# Microcontroller.net
KiCad netlist of a schematic drawn in Altium Designer
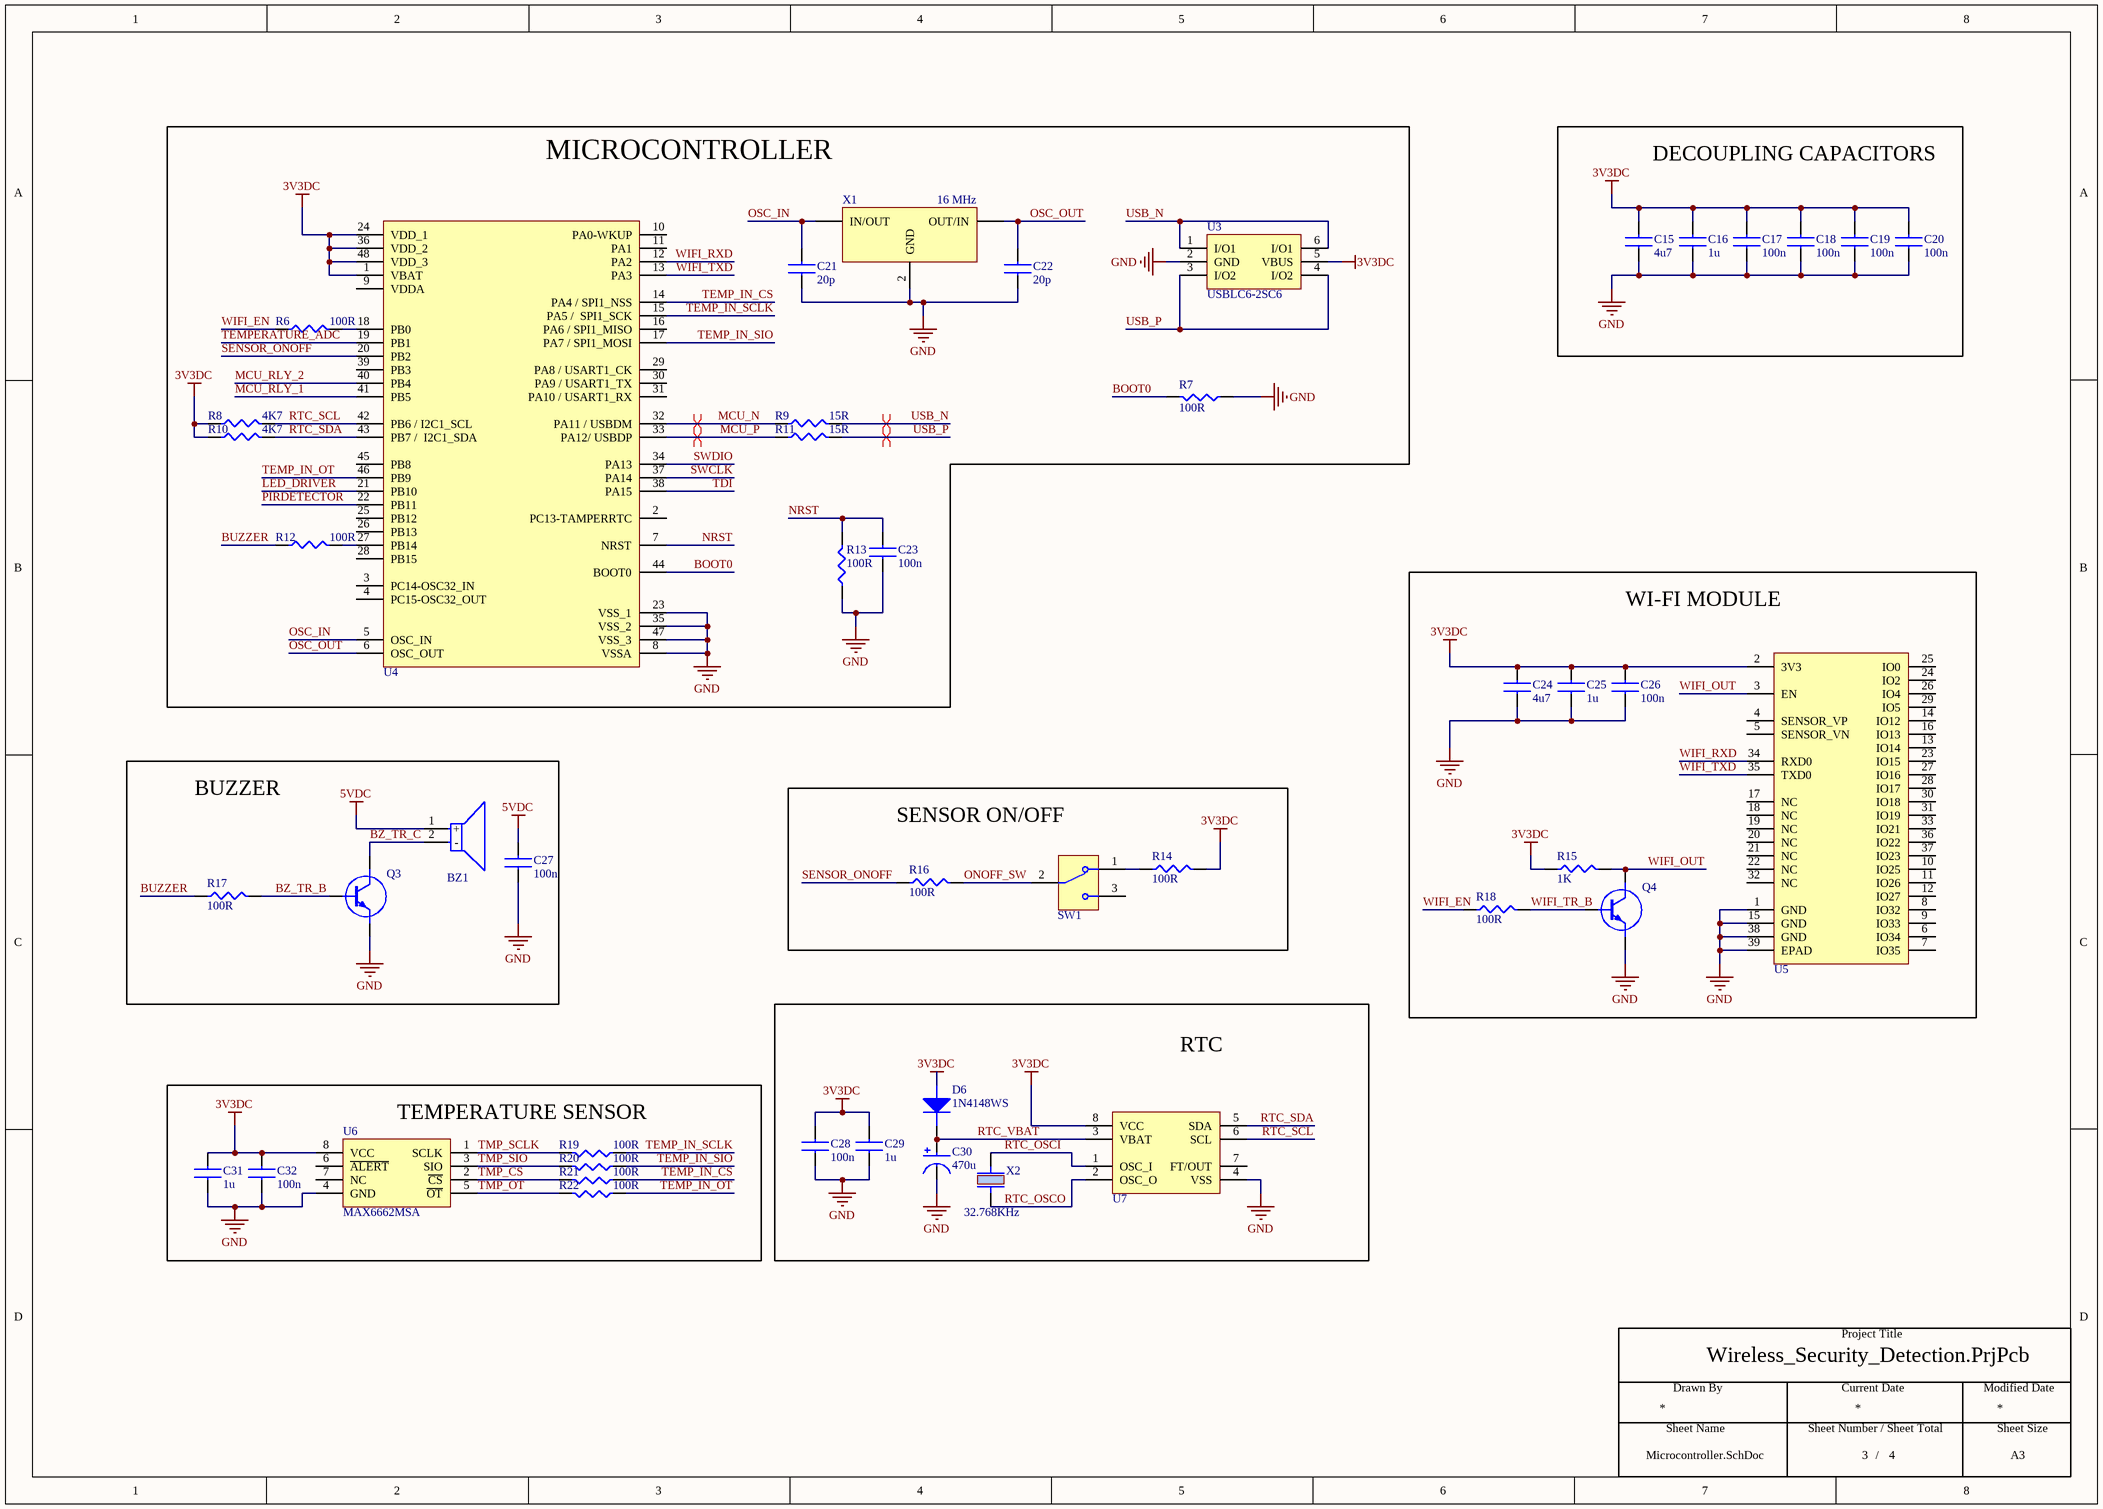
[diagram p0: Microcontroller.SchDoc]

(export (version "E")
  (design (tool "Eeschema 10.0.6"))
  (components
    (comp (ref "BZ1")
      (value "CMI-9605IC-0580T")
      (footprint "CMI-9605IC-0580T")
      (description "Audio Buzzer Magnetic 3VDC 7VDC 30mA 5VDC 85dB 2600Hz to 2800Hz Through Hole Pin Box")
      (fields (field (name "MANUFACTURER") "CUI Devices") (field (name "DESIGNED BY") "UK"))
      (libsource (lib "UKLIB") (part "CMI-9605IC-0580T"))
    )
    (comp (ref "C15")
      (value "4u7")
      (footprint "CAPACITOR 0805 - duplicate")
      (description "Multilayer Ceramic Capacitor, 4.7 uF, 25 V, ± 10%, X5R, 0805 [2012 Metric]")
      (fields
        (field (name "MANUFACTURER") "Samsung")
        (field (name "MANUFACTURER PART NUMBER") "CL21A475KAQNNNE")
        (field (name "DESIGNED BY") "UK")
      )
      (libsource (lib "UKLIB") (part "CAP CER 4.7uF 0805"))
    )
    (comp (ref "C16")
      (value "1u")
      (footprint "CAPACITOR 0805 - duplicate")
      (description "Multilayer Ceramic Capacitor, 1 uF, 50 V, ± 10%, X7R, 0805 [2012 Metric]")
      (fields
        (field (name "MANUFACTURER") "Samsung")
        (field (name "MANUFACTURER PART NUMBER") "CL21B105KBFNNNE")
        (field (name "DESIGNED BY") "UK")
      )
      (libsource (lib "UKLIB") (part "CAP CER 1uF 0805"))
    )
    (comp (ref "C17")
      (value "100n")
      (footprint "Capacitor 0603")
      (description "Multilayer Ceramic Capacitor, 0.1 uF, 50 V, ± 10%, X7R, 0603 [1608 Metric]")
      (fields
        (field (name "MANUFACTURER") "KEMET")
        (field (name "MANUFACTURER PART NUMBER") "C0603C104K5RACTU")
        (field (name "DESIGNED BY") "UK")
      )
      (libsource (lib "UKLIB") (part "CAP CER 100nF 0603"))
    )
    (comp (ref "C18")
      (value "100n")
      (footprint "Capacitor 0603")
      (description "Multilayer Ceramic Capacitor, 0.1 uF, 50 V, ± 10%, X7R, 0603 [1608 Metric]")
      (fields
        (field (name "MANUFACTURER") "KEMET")
        (field (name "MANUFACTURER PART NUMBER") "C0603C104K5RACTU")
        (field (name "DESIGNED BY") "UK")
      )
      (libsource (lib "UKLIB") (part "CAP CER 100nF 0603"))
    )
    (comp (ref "C19")
      (value "100n")
      (footprint "Capacitor 0603")
      (description "Multilayer Ceramic Capacitor, 0.1 uF, 50 V, ± 10%, X7R, 0603 [1608 Metric]")
      (fields
        (field (name "MANUFACTURER") "KEMET")
        (field (name "MANUFACTURER PART NUMBER") "C0603C104K5RACTU")
        (field (name "DESIGNED BY") "UK")
      )
      (libsource (lib "UKLIB") (part "CAP CER 100nF 0603"))
    )
    (comp (ref "C20")
      (value "100n")
      (footprint "Capacitor 0603")
      (description "Multilayer Ceramic Capacitor, 0.1 uF, 50 V, ± 10%, X7R, 0603 [1608 Metric]")
      (fields
        (field (name "MANUFACTURER") "KEMET")
        (field (name "MANUFACTURER PART NUMBER") "C0603C104K5RACTU")
        (field (name "DESIGNED BY") "UK")
      )
      (libsource (lib "UKLIB") (part "CAP CER 100nF 0603"))
    )
    (comp (ref "C21")
      (value "20p")
      (footprint "CAPACITOR 0603")
      (description "Multilayer Ceramic Capacitor, 20 pF, 50 V, ± 5%, C0G (NP0), 0603 [1608 Metric]")
      (fields
        (field (name "MANUFACTURER") "Samsung")
        (field (name "MANUFACTURER PART NUMBER") "CL10C200JB8NNNC")
        (field (name "DESIGNED BY") "UK")
      )
      (libsource (lib "UKLIB") (part "CAP CER 20pF 0603"))
    )
    (comp (ref "C22")
      (value "20p")
      (footprint "CAPACITOR 0603")
      (description "Multilayer Ceramic Capacitor, 20 pF, 50 V, ± 5%, C0G (NP0), 0603 [1608 Metric]")
      (fields
        (field (name "MANUFACTURER") "Samsung")
        (field (name "MANUFACTURER PART NUMBER") "CL10C200JB8NNNC")
        (field (name "DESIGNED BY") "UK")
      )
      (libsource (lib "UKLIB") (part "CAP CER 20pF 0603"))
    )
    (comp (ref "C23")
      (value "100n")
      (footprint "CAPACITOR 0805 - duplicate")
      (description "Multilayer Ceramic Capacitor, 0.1 uF, 50 V, ± 10%, X7R, 0805 [2012 Metric]")
      (fields
        (field (name "MANUFACTURER") "Samsung")
        (field (name "MANUFACTURER PART NUMBER") "CL21B104KBCNNNC")
        (field (name "DESIGNED BY") "UK")
      )
      (libsource (lib "UKLIB") (part "CAP CER 100nF 0805"))
    )
    (comp (ref "C24")
      (value "4u7")
      (footprint "CAPACITOR 0805 - duplicate")
      (description "Multilayer Ceramic Capacitor, 4.7 uF, 25 V, ± 10%, X5R, 0805 [2012 Metric]")
      (fields
        (field (name "MANUFACTURER") "Samsung")
        (field (name "MANUFACTURER PART NUMBER") "CL21A475KAQNNNE")
        (field (name "DESIGNED BY") "UK")
      )
      (libsource (lib "UKLIB") (part "CAP CER 4.7uF 0805"))
    )
    (comp (ref "C25")
      (value "1u")
      (footprint "CAPACITOR 0805 - duplicate")
      (description "Multilayer Ceramic Capacitor, 1 uF, 50 V, ± 10%, X7R, 0805 [2012 Metric]")
      (fields
        (field (name "MANUFACTURER") "Samsung")
        (field (name "MANUFACTURER PART NUMBER") "CL21B105KBFNNNE")
        (field (name "DESIGNED BY") "UK")
      )
      (libsource (lib "UKLIB") (part "CAP CER 1uF 0805"))
    )
    (comp (ref "C26")
      (value "100n")
      (footprint "CAPACITOR 0805 - duplicate")
      (description "Multilayer Ceramic Capacitor, 0.1 uF, 50 V, ± 10%, X7R, 0805 [2012 Metric]")
      (fields
        (field (name "MANUFACTURER") "Samsung")
        (field (name "MANUFACTURER PART NUMBER") "CL21B104KBCNNNC")
        (field (name "DESIGNED BY") "UK")
      )
      (libsource (lib "UKLIB") (part "CAP CER 100nF 0805"))
    )
    (comp (ref "C27")
      (value "100n")
      (footprint "CAPACITOR 0805 - duplicate")
      (description "Multilayer Ceramic Capacitor, 0.1 uF, 50 V, ± 10%, X7R, 0805 [2012 Metric]")
      (fields
        (field (name "MANUFACTURER") "Samsung")
        (field (name "MANUFACTURER PART NUMBER") "CL21B104KBCNNNC")
        (field (name "DESIGNED BY") "UK")
      )
      (libsource (lib "UKLIB") (part "CAP CER 100nF 0805"))
    )
    (comp (ref "C28")
      (value "100n")
      (footprint "CAPACITOR 0805 - duplicate")
      (description "Multilayer Ceramic Capacitor, 0.1 uF, 50 V, ± 10%, X7R, 0805 [2012 Metric]")
      (fields
        (field (name "MANUFACTURER") "Samsung")
        (field (name "MANUFACTURER PART NUMBER") "CL21B104KBCNNNC")
        (field (name "DESIGNED BY") "UK")
      )
      (libsource (lib "UKLIB") (part "CAP CER 100nF 0805"))
    )
    (comp (ref "C29")
      (value "1u")
      (footprint "CAPACITOR 0805 - duplicate")
      (description "Multilayer Ceramic Capacitor, 1 uF, 50 V, ± 10%, X7R, 0805 [2012 Metric]")
      (fields
        (field (name "MANUFACTURER") "Samsung")
        (field (name "MANUFACTURER PART NUMBER") "CL21B105KBFNNNE")
        (field (name "DESIGNED BY") "UK")
      )
      (libsource (lib "UKLIB") (part "CAP CER 1uF 0805"))
    )
    (comp (ref "C30")
      (value "470u")
      (footprint "CAP ALUM RADIAL TH D10 L20 P5")
      (description "Radial Electrolytic Aluminium Capacitor, 470uF, 50VDC, 20%")
      (fields
        (field (name "MANUFACTURER") "KEMET")
        (field (name "MANUFACTURER PART NUMBER") "ESH477M050AH4AA")
        (field (name "DESIGNED BY") "UK")
      )
      (libsource (lib "UKLIB") (part "CAP ALUM 470uF RADIAL TH"))
    )
    (comp (ref "C31")
      (value "1u")
      (footprint "CAPACITOR 0805 - duplicate")
      (description "Multilayer Ceramic Capacitor, 1 uF, 50 V, ± 10%, X7R, 0805 [2012 Metric]")
      (fields
        (field (name "MANUFACTURER") "Samsung")
        (field (name "MANUFACTURER PART NUMBER") "CL21B105KBFNNNE")
        (field (name "DESIGNED BY") "UK")
      )
      (libsource (lib "UKLIB") (part "CAP CER 1uF 0805"))
    )
    (comp (ref "C32")
      (value "100n")
      (footprint "CAPACITOR 0805 - duplicate")
      (description "Multilayer Ceramic Capacitor, 0.1 uF, 50 V, ± 10%, X7R, 0805 [2012 Metric]")
      (fields
        (field (name "MANUFACTURER") "Samsung")
        (field (name "MANUFACTURER PART NUMBER") "CL21B104KBCNNNC")
        (field (name "DESIGNED BY") "UK")
      )
      (libsource (lib "UKLIB") (part "CAP CER 100nF 0805"))
    )
    (comp (ref "D6")
      (value "1N4148WS")
      (footprint "SOD-323F")
      (description "Diode Ultra Fast Recovery Rectifier 75V 0.15A 2-Pin SOD-323F T/R")
      (fields (field (name "MANUFACTURER") "ON Semiconductor / Fairchild") (field (name "DESIGNED BY") "UK"))
      (libsource (lib "UKLIB") (part "1N4148WS"))
    )
    (comp (ref "Q3")
      (value "MMBT3904-7-F")
      (footprint "SOT-23F")
      (description "Transistor General Purpose BJT NPN 40 Volt 0.2A Automotive 3-Pin SOT-23")
      (fields (field (name "MANUFACTURER") "Diodes Zetex") (field (name "DESIGNED BY") "UK"))
      (libsource (lib "UKLIB") (part "MMBT3904-7-F"))
    )
    (comp (ref "Q4")
      (value "MMBT3904-7-F")
      (footprint "SOT-23F")
      (description "Transistor General Purpose BJT NPN 40 Volt 0.2A Automotive 3-Pin SOT-23")
      (fields (field (name "MANUFACTURER") "Diodes Zetex") (field (name "DESIGNED BY") "UK"))
      (libsource (lib "UKLIB") (part "MMBT3904-7-F"))
    )
    (comp (ref "R6")
      (value "100R")
      (footprint "Resistor 0603")
      (description "SMD Chip Resistor, 100 Ohm, ± 5%, 100 mW, 0603 [1608 Metric], Thick Film, General Purpose")
      (fields
        (field (name "MANUFACTURER") "Yageo")
        (field (name "MANUFACTURER PART NUMBER") "RC0603JR-07100RL")
        (field (name "DESIGNED BY") "UK")
      )
      (libsource (lib "UKLIB") (part "RES 100R 0603"))
    )
    (comp (ref "R7")
      (value "100R")
      (footprint "Resistor 0603")
      (description "SMD Chip Resistor, 100 Ohm, ± 5%, 100 mW, 0603 [1608 Metric], Thick Film, General Purpose")
      (fields
        (field (name "MANUFACTURER") "Yageo")
        (field (name "MANUFACTURER PART NUMBER") "RC0603JR-07100RL")
        (field (name "DESIGNED BY") "UK")
      )
      (libsource (lib "UKLIB") (part "RES 100R 0603"))
    )
    (comp (ref "R8")
      (value "4K7")
      (footprint "Resistor 0603")
      (description "SMD Chip Resistor, 4.7 kOhm, ± 5%, 100 mW, 0603 [1608 Metric], Thick Film, General Purpose")
      (fields
        (field (name "MANUFACTURER") "Yageo")
        (field (name "MANUFACTURER PART NUMBER") "RC0603JR-074K7L")
        (field (name "DESIGNED BY") "UK")
      )
      (libsource (lib "UKLIB") (part "RES 4K7 0603"))
    )
    (comp (ref "R9")
      (value "15R")
      (footprint "Resistor 0603")
      (description "SMD Chip Resistor, 15 Ohm, ± 5%, 100 mW, 0603 [1608 Metric], Thick Film, General Purpose")
      (fields
        (field (name "MANUFACTURER") "Yageo")
        (field (name "MANUFACTURER PART NUMBER") "RC0603JR-0715RL")
        (field (name "DESIGNED BY") "UK")
      )
      (libsource (lib "UKLIB") (part "RES 15R 0603"))
    )
    (comp (ref "R10")
      (value "4K7")
      (footprint "Resistor 0603")
      (description "SMD Chip Resistor, 4.7 kOhm, ± 5%, 100 mW, 0603 [1608 Metric], Thick Film, General Purpose")
      (fields
        (field (name "MANUFACTURER") "Yageo")
        (field (name "MANUFACTURER PART NUMBER") "RC0603JR-074K7L")
        (field (name "DESIGNED BY") "UK")
      )
      (libsource (lib "UKLIB") (part "RES 4K7 0603"))
    )
    (comp (ref "R11")
      (value "15R")
      (footprint "Resistor 0603")
      (description "SMD Chip Resistor, 15 Ohm, ± 5%, 100 mW, 0603 [1608 Metric], Thick Film, General Purpose")
      (fields
        (field (name "MANUFACTURER") "Yageo")
        (field (name "MANUFACTURER PART NUMBER") "RC0603JR-0715RL")
        (field (name "DESIGNED BY") "UK")
      )
      (libsource (lib "UKLIB") (part "RES 15R 0603"))
    )
    (comp (ref "R12")
      (value "100R")
      (footprint "Resistor 0603")
      (description "SMD Chip Resistor, 100 Ohm, ± 5%, 100 mW, 0603 [1608 Metric], Thick Film, General Purpose")
      (fields
        (field (name "MANUFACTURER") "Yageo")
        (field (name "MANUFACTURER PART NUMBER") "RC0603JR-07100RL")
        (field (name "DESIGNED BY") "UK")
      )
      (libsource (lib "UKLIB") (part "RES 100R 0603"))
    )
    (comp (ref "R13")
      (value "100R")
      (footprint "Resistor 0603")
      (description "SMD Chip Resistor, 100 Ohm, ± 5%, 100 mW, 0603 [1608 Metric], Thick Film, General Purpose")
      (fields
        (field (name "MANUFACTURER") "Yageo")
        (field (name "MANUFACTURER PART NUMBER") "RC0603JR-07100RL")
        (field (name "DESIGNED BY") "UK")
      )
      (libsource (lib "UKLIB") (part "RES 100R 0603"))
    )
    (comp (ref "R14")
      (value "100R")
      (footprint "Resistor 0603")
      (description "SMD Chip Resistor, 100 Ohm, ± 5%, 100 mW, 0603 [1608 Metric], Thick Film, General Purpose")
      (fields
        (field (name "MANUFACTURER") "Yageo")
        (field (name "MANUFACTURER PART NUMBER") "RC0603JR-07100RL")
        (field (name "DESIGNED BY") "UK")
      )
      (libsource (lib "UKLIB") (part "RES 100R 0603"))
    )
    (comp (ref "R15")
      (value "1K")
      (footprint "Resistor 0603")
      (description "SMD Chip Resistor, 1 kOhm, ± 1%, 100 mW, 0603 [1608 Metric], Thick Film, General Purpose")
      (fields
        (field (name "MANUFACTURER") "Yageo")
        (field (name "MANUFACTURER PART NUMBER") "RC0603FR-071KL")
        (field (name "DESIGNED BY") "UK")
      )
      (libsource (lib "UKLIB") (part "RES 1K 0603"))
    )
    (comp (ref "R16")
      (value "100R")
      (footprint "Resistor 0603")
      (description "SMD Chip Resistor, 100 Ohm, ± 5%, 100 mW, 0603 [1608 Metric], Thick Film, General Purpose")
      (fields
        (field (name "MANUFACTURER") "Yageo")
        (field (name "MANUFACTURER PART NUMBER") "RC0603JR-07100RL")
        (field (name "DESIGNED BY") "UK")
      )
      (libsource (lib "UKLIB") (part "RES 100R 0603"))
    )
    (comp (ref "R17")
      (value "100R")
      (footprint "Resistor 0603")
      (description "SMD Chip Resistor, 100 Ohm, ± 5%, 100 mW, 0603 [1608 Metric], Thick Film, General Purpose")
      (fields
        (field (name "MANUFACTURER") "Yageo")
        (field (name "MANUFACTURER PART NUMBER") "RC0603JR-07100RL")
        (field (name "DESIGNED BY") "UK")
      )
      (libsource (lib "UKLIB") (part "RES 100R 0603"))
    )
    (comp (ref "R18")
      (value "100R")
      (footprint "Resistor 0603")
      (description "SMD Chip Resistor, 100 Ohm, ± 5%, 100 mW, 0603 [1608 Metric], Thick Film, General Purpose")
      (fields
        (field (name "MANUFACTURER") "Yageo")
        (field (name "MANUFACTURER PART NUMBER") "RC0603JR-07100RL")
        (field (name "DESIGNED BY") "UK")
      )
      (libsource (lib "UKLIB") (part "RES 100R 0603"))
    )
    (comp (ref "R19")
      (value "100R")
      (footprint "Resistor 0603")
      (description "SMD Chip Resistor, 100 Ohm, ± 5%, 100 mW, 0603 [1608 Metric], Thick Film, General Purpose")
      (fields
        (field (name "MANUFACTURER") "Yageo")
        (field (name "MANUFACTURER PART NUMBER") "RC0603JR-07100RL")
        (field (name "DESIGNED BY") "UK")
      )
      (libsource (lib "UKLIB") (part "RES 100R 0603"))
    )
    (comp (ref "R20")
      (value "100R")
      (footprint "Resistor 0603")
      (description "SMD Chip Resistor, 100 Ohm, ± 5%, 100 mW, 0603 [1608 Metric], Thick Film, General Purpose")
      (fields
        (field (name "MANUFACTURER") "Yageo")
        (field (name "MANUFACTURER PART NUMBER") "RC0603JR-07100RL")
        (field (name "DESIGNED BY") "UK")
      )
      (libsource (lib "UKLIB") (part "RES 100R 0603"))
    )
    (comp (ref "R21")
      (value "100R")
      (footprint "Resistor 0603")
      (description "SMD Chip Resistor, 100 Ohm, ± 5%, 100 mW, 0603 [1608 Metric], Thick Film, General Purpose")
      (fields
        (field (name "MANUFACTURER") "Yageo")
        (field (name "MANUFACTURER PART NUMBER") "RC0603JR-07100RL")
        (field (name "DESIGNED BY") "UK")
      )
      (libsource (lib "UKLIB") (part "RES 100R 0603"))
    )
    (comp (ref "R22")
      (value "100R")
      (footprint "Resistor 0603")
      (description "SMD Chip Resistor, 100 Ohm, ± 5%, 100 mW, 0603 [1608 Metric], Thick Film, General Purpose")
      (fields
        (field (name "MANUFACTURER") "Yageo")
        (field (name "MANUFACTURER PART NUMBER") "RC0603JR-07100RL")
        (field (name "DESIGNED BY") "UK")
      )
      (libsource (lib "UKLIB") (part "RES 100R 0603"))
    )
    (comp (ref "SW1")
      (value "EG1215AA")
      (footprint "EG1215AA")
      (description "Slide Switch, SPDT, 0.025A, 24V, SMD")
      (fields (field (name "MANUFACTURER") "E-Switch") (field (name "DESIGNED BY") "UK"))
      (libsource (lib "UKLIB") (part "EG1215AA"))
    )
    (comp (ref "U3")
      (value "USBLC6-2SC6")
      (footprint "SOT23-6L")
      (description "ESD Suppressor Diode Arrays Uni-Dir 15kV@Air Gap/8kV@Contact Disc 6-Pin SOT-23 T/R")
      (fields (field (name "MANUFACTURER") "STMicroelectronics") (field (name "DESIGNED BY") "UK"))
      (libsource (lib "UKLIB") (part "USBLC6-2SC6"))
    )
    (comp (ref "U4")
      (value "STM32F103C6T6A")
      (footprint "LQFP48")
      (description "MCU 32-bit STM32F ARM Cortex M3 RISC 32KB Flash 2.5V/3.3V 48-Pin LQFP Tray")
      (fields (field (name "MANUFACTURER") "STMicroelectronics") (field (name "DESIGNED BY") "UK"))
      (libsource (lib "UKLIB") (part "STM32F103C6T6A"))
    )
    (comp (ref "U5")
      (value "ESP32-WROOM-32E")
      (footprint "ESP32­WROOM­32E")
      (description "WiFi-Module 802.11/BT 2, 4-2, 5GHz 150Mb/s")
      (fields
        (field (name "MANUFACTURER") "Espressif Systems")
        (field (name "MANUFACTURER PART NUMBER") "ESP32-WROOM-32E(M113EH3200PH3Q0)")
        (field (name "DESIGNED BY") "UK")
      )
      (libsource (lib "UKLIB") (part "ESP32-WROOM-32E (4MB)"))
    )
    (comp (ref "U6")
      (value "MAX6662MSA")
      (footprint "SOIC-8")
      (description "Temp Sensor Digital Serial (3-Wire, SPI) 8-Pin SOIC N Tube")
      (fields
        (field (name "MANUFACTURER") "Maxim")
        (field (name "MANUFACTURER PART NUMBER") "MAX6662MSA+")
        (field (name "DESIGNED BY") "UK")
      )
      (libsource (lib "UKLIB") (part "MAX6662MSA"))
    )
    (comp (ref "U7")
      (value "M41T00M6F")
      (footprint "SOIC-8")
      (description "Real Time Clock (RTC) IC Clock/Calendar I2C, 2-Wire Serial 8-SOIC (0.154\", 3.90mm Width)")
      (fields (field (name "MANUFACTURER") "STMicroelectronics") (field (name "DESIGNED BY") "UK"))
      (libsource (lib "UKLIB") (part "M41T00M6F"))
    )
    (comp (ref "X1")
      (value "16 MHz")
      (footprint "ECS-160-20-30B-TR 16MHZ")
      (description "Crystal 16MHz ±30ppm (Tol) ±50ppm (Stability) 20pF FUND 50Ohm 4-Pin Mini-SMD T/R")
      (fields
        (field (name "MANUFACTURER") "ECS International")
        (field (name "MANUFACTURER PART NUMBER") "ECS-160-20-30B-TR")
        (field (name "DESIGNED BY") "UK")
      )
      (libsource (lib "UKLIB") (part "ECS-160-20-30B-TR"))
    )
    (comp (ref "X2")
      (value "32.768KHz")
      (footprint "ABS05-32.768KHZ-T")
      (description "Crystal 32.768KHz ±20ppm (Tol) 12.5pF Flexural 90000Ohm 2-Pin CSMD T/R")
      (fields
        (field (name "MANUFACTURER") "Abracon")
        (field (name "MANUFACTURER PART NUMBER") "ABS05-32.768KHZ-T")
        (field (name "DESIGNED BY") "UK")
      )
      (libsource (lib "UKLIB") (part "ABS05-32.768KHZ-T"))
    )
  )
  (nets
    (net (code "1") (name "/BOOT0") (class "Default")
      (node (ref "R7") (pin "2") (pinfunction "2_2") (pintype "passive"))
      (node (ref "U4") (pin "44") (pinfunction "BOOT0_44") (pintype "passive"))
    )
    (net (code "2") (name "/BUZZER") (class "Default")
      (node (ref "R12") (pin "1") (pinfunction "1_1") (pintype "passive"))
      (node (ref "R17") (pin "1") (pinfunction "1_1") (pintype "passive"))
    )
    (net (code "3") (name "/BZ_TR_B") (class "Default")
      (node (ref "Q3") (pin "1") (pinfunction "B_1") (pintype "passive"))
      (node (ref "R17") (pin "2") (pinfunction "2_2") (pintype "passive"))
    )
    (net (code "4") (name "/BZ_TR_C") (class "Default")
      (node (ref "BZ1") (pin "2") (pinfunction "-_2") (pintype "passive"))
      (node (ref "Q3") (pin "3") (pinfunction "C_3") (pintype "passive"))
    )
    (net (code "5") (name "/LED_DRIVER") (class "Default")
      (node (ref "U4") (pin "21") (pinfunction "PB10_21") (pintype "passive"))
    )
    (net (code "6") (name "/MCU_N") (class "Default")
      (node (ref "R9") (pin "1") (pinfunction "1_1") (pintype "passive"))
      (node (ref "U4") (pin "32") (pinfunction "PA11_/_USBDM_32") (pintype "passive"))
    )
    (net (code "7") (name "/MCU_P") (class "Default")
      (node (ref "R11") (pin "1") (pinfunction "1_1") (pintype "passive"))
      (node (ref "U4") (pin "33") (pinfunction "PA12/_USBDP_33") (pintype "passive"))
    )
    (net (code "8") (name "/MCU_RLY_1") (class "Default")
      (node (ref "U4") (pin "41") (pinfunction "PB5_41") (pintype "passive"))
    )
    (net (code "9") (name "/MCU_RLY_2") (class "Default")
      (node (ref "U4") (pin "40") (pinfunction "PB4_40") (pintype "passive"))
    )
    (net (code "10") (name "/NRST") (class "Default")
      (node (ref "C23") (pin "2") (pinfunction "2_2") (pintype "passive"))
      (node (ref "R13") (pin "2") (pinfunction "2_2") (pintype "passive"))
      (node (ref "U4") (pin "7") (pinfunction "NRST_7") (pintype "passive"))
    )
    (net (code "11") (name "/ONOFF_SW") (class "Default")
      (node (ref "R16") (pin "2") (pinfunction "2_2") (pintype "passive"))
      (node (ref "SW1") (pin "2") (pinfunction "2_2") (pintype "passive"))
    )
    (net (code "12") (name "/OSC_IN") (class "Default")
      (node (ref "C21") (pin "2") (pinfunction "2_2") (pintype "passive"))
      (node (ref "U4") (pin "5") (pinfunction "OSC_IN_5") (pintype "passive"))
      (node (ref "X1") (pin "1") (pinfunction "IN/OUT_1") (pintype "passive"))
    )
    (net (code "13") (name "/OSC_OUT") (class "Default")
      (node (ref "C22") (pin "2") (pinfunction "2_2") (pintype "passive"))
      (node (ref "U4") (pin "6") (pinfunction "OSC_OUT_6") (pintype "passive"))
      (node (ref "X1") (pin "3") (pinfunction "OUT/IN_3") (pintype "passive"))
    )
    (net (code "14") (name "/PIRDETECTOR") (class "Default")
      (node (ref "U4") (pin "22") (pinfunction "PB11_22") (pintype "passive"))
    )
    (net (code "15") (name "/RTC_OSCI") (class "Default")
      (node (ref "U7") (pin "1") (pinfunction "OSC_I_1") (pintype "passive"))
      (node (ref "X2") (pin "2") (pinfunction "2_2") (pintype "passive"))
    )
    (net (code "16") (name "/RTC_OSCO") (class "Default")
      (node (ref "U7") (pin "2") (pinfunction "OSC_O_2") (pintype "passive"))
      (node (ref "X2") (pin "1") (pinfunction "1_1") (pintype "passive"))
    )
    (net (code "17") (name "/RTC_SCL") (class "Default")
      (node (ref "R8") (pin "2") (pinfunction "2_2") (pintype "passive"))
      (node (ref "U4") (pin "42") (pinfunction "PB6_/_I2C1_SCL_42") (pintype "passive"))
      (node (ref "U7") (pin "6") (pinfunction "SCL_6") (pintype "passive"))
    )
    (net (code "18") (name "/RTC_SDA") (class "Default")
      (node (ref "R10") (pin "2") (pinfunction "2_2") (pintype "passive"))
      (node (ref "U4") (pin "43") (pinfunction "PB7_/__I2C1_SDA_43") (pintype "passive"))
      (node (ref "U7") (pin "5") (pinfunction "SDA_5") (pintype "passive"))
    )
    (net (code "19") (name "/RTC_VBAT") (class "Default")
      (node (ref "C30") (pin "1") (pinfunction "1_1") (pintype "passive"))
      (node (ref "D6") (pin "2") (pinfunction "C_2") (pintype "passive"))
      (node (ref "U7") (pin "3") (pinfunction "VBAT_3") (pintype "passive"))
    )
    (net (code "20") (name "/SENSOR_ONOFF") (class "Default")
      (node (ref "R16") (pin "1") (pinfunction "1_1") (pintype "passive"))
      (node (ref "U4") (pin "20") (pinfunction "PB2_20") (pintype "passive"))
    )
    (net (code "21") (name "/SWCLK") (class "Default")
      (node (ref "U4") (pin "37") (pinfunction "PA14_37") (pintype "passive"))
    )
    (net (code "22") (name "/SWDIO") (class "Default")
      (node (ref "U4") (pin "34") (pinfunction "PA13_34") (pintype "passive"))
    )
    (net (code "23") (name "/TDI") (class "Default")
      (node (ref "U4") (pin "38") (pinfunction "PA15_38") (pintype "passive"))
    )
    (net (code "24") (name "/TEMPERATURE_ADC") (class "Default")
      (node (ref "U4") (pin "19") (pinfunction "PB1_19") (pintype "passive"))
    )
    (net (code "25") (name "/TEMP_IN_CS") (class "Default")
      (node (ref "R21") (pin "1") (pinfunction "1_1") (pintype "passive"))
      (node (ref "U4") (pin "14") (pinfunction "PA4_/_SPI1_NSS_14") (pintype "passive"))
    )
    (net (code "26") (name "/TEMP_IN_OT") (class "Default")
      (node (ref "R22") (pin "1") (pinfunction "1_1") (pintype "passive"))
      (node (ref "U4") (pin "46") (pinfunction "PB9_46") (pintype "passive"))
    )
    (net (code "27") (name "/TEMP_IN_SCLK") (class "Default")
      (node (ref "R19") (pin "1") (pinfunction "1_1") (pintype "passive"))
      (node (ref "U4") (pin "15") (pinfunction "PA5_/__SPI1_SCK_15") (pintype "passive"))
    )
    (net (code "28") (name "/TEMP_IN_SIO") (class "Default")
      (node (ref "R20") (pin "1") (pinfunction "1_1") (pintype "passive"))
      (node (ref "U4") (pin "17") (pinfunction "PA7_/_SPI1_MOSI_17") (pintype "passive"))
    )
    (net (code "29") (name "/TMP_CS") (class "Default")
      (node (ref "R21") (pin "2") (pinfunction "2_2") (pintype "passive"))
      (node (ref "U6") (pin "2") (pinfunction "~{CS}_2") (pintype "passive"))
    )
    (net (code "30") (name "/TMP_OT") (class "Default")
      (node (ref "R22") (pin "2") (pinfunction "2_2") (pintype "passive"))
      (node (ref "U6") (pin "5") (pinfunction "~{OT}_5") (pintype "passive"))
    )
    (net (code "31") (name "/TMP_SCLK") (class "Default")
      (node (ref "R19") (pin "2") (pinfunction "2_2") (pintype "passive"))
      (node (ref "U6") (pin "1") (pinfunction "SCLK_1") (pintype "passive"))
    )
    (net (code "32") (name "/TMP_SIO") (class "Default")
      (node (ref "R20") (pin "2") (pinfunction "2_2") (pintype "passive"))
      (node (ref "U6") (pin "3") (pinfunction "SIO_3") (pintype "passive"))
    )
    (net (code "33") (name "/USB_N") (class "Default")
      (node (ref "R9") (pin "2") (pinfunction "2_2") (pintype "passive"))
      (node (ref "U3") (pin "1") (pinfunction "I/O1_1") (pintype "passive"))
      (node (ref "U3") (pin "6") (pinfunction "I/O1_6") (pintype "passive"))
    )
    (net (code "34") (name "/USB_P") (class "Default")
      (node (ref "R11") (pin "2") (pinfunction "2_2") (pintype "passive"))
      (node (ref "U3") (pin "3") (pinfunction "I/O2_3") (pintype "passive"))
      (node (ref "U3") (pin "4") (pinfunction "I/O2_4") (pintype "passive"))
    )
    (net (code "35") (name "/WIFI_EN") (class "Default")
      (node (ref "R18") (pin "1") (pinfunction "1_1") (pintype "passive"))
      (node (ref "R6") (pin "1") (pinfunction "1_1") (pintype "passive"))
    )
    (net (code "36") (name "/WIFI_OUT") (class "Default")
      (node (ref "Q4") (pin "3") (pinfunction "C_3") (pintype "passive"))
      (node (ref "R15") (pin "2") (pinfunction "2_2") (pintype "passive"))
      (node (ref "U5") (pin "3") (pinfunction "EN_3") (pintype "passive"))
    )
    (net (code "37") (name "/WIFI_RXD") (class "Default")
      (node (ref "U4") (pin "12") (pinfunction "PA2_12") (pintype "passive"))
      (node (ref "U5") (pin "34") (pinfunction "RXD0_34") (pintype "passive"))
    )
    (net (code "38") (name "/WIFI_TR_B") (class "Default")
      (node (ref "Q4") (pin "1") (pinfunction "B_1") (pintype "passive"))
      (node (ref "R18") (pin "2") (pinfunction "2_2") (pintype "passive"))
    )
    (net (code "39") (name "/WIFI_TXD") (class "Default")
      (node (ref "U4") (pin "13") (pinfunction "PA3_13") (pintype "passive"))
      (node (ref "U5") (pin "35") (pinfunction "TXD0_35") (pintype "passive"))
    )
    (net (code "40") (name "3V3DC") (class "Default")
      (node (ref "C15") (pin "2") (pinfunction "2_2") (pintype "passive"))
      (node (ref "C16") (pin "2") (pinfunction "2_2") (pintype "passive"))
      (node (ref "C17") (pin "2") (pinfunction "2_2") (pintype "passive"))
      (node (ref "C18") (pin "2") (pinfunction "2_2") (pintype "passive"))
      (node (ref "C19") (pin "2") (pinfunction "2_2") (pintype "passive"))
      (node (ref "C20") (pin "2") (pinfunction "2_2") (pintype "passive"))
      (node (ref "C24") (pin "2") (pinfunction "2_2") (pintype "passive"))
      (node (ref "C25") (pin "2") (pinfunction "2_2") (pintype "passive"))
      (node (ref "C26") (pin "2") (pinfunction "2_2") (pintype "passive"))
      (node (ref "C28") (pin "2") (pinfunction "2_2") (pintype "passive"))
      (node (ref "C29") (pin "2") (pinfunction "2_2") (pintype "passive"))
      (node (ref "C31") (pin "2") (pinfunction "2_2") (pintype "passive"))
      (node (ref "C32") (pin "2") (pinfunction "2_2") (pintype "passive"))
      (node (ref "D6") (pin "1") (pinfunction "A_1") (pintype "passive"))
      (node (ref "R10") (pin "1") (pinfunction "1_1") (pintype "passive"))
      (node (ref "R14") (pin "2") (pinfunction "2_2") (pintype "passive"))
      (node (ref "R15") (pin "1") (pinfunction "1_1") (pintype "passive"))
      (node (ref "R8") (pin "1") (pinfunction "1_1") (pintype "passive"))
      (node (ref "U3") (pin "5") (pinfunction "VBUS_5") (pintype "passive"))
      (node (ref "U4") (pin "1") (pinfunction "VBAT_1") (pintype "passive"))
      (node (ref "U4") (pin "24") (pinfunction "VDD_1_24") (pintype "passive"))
      (node (ref "U4") (pin "36") (pinfunction "VDD_2_36") (pintype "passive"))
      (node (ref "U4") (pin "48") (pinfunction "VDD_3_48") (pintype "passive"))
      (node (ref "U5") (pin "2") (pinfunction "3V3_2") (pintype "passive"))
      (node (ref "U6") (pin "8") (pinfunction "VCC_8") (pintype "passive"))
      (node (ref "U7") (pin "8") (pinfunction "VCC_8") (pintype "passive"))
    )
    (net (code "41") (name "5VDC") (class "Default")
      (node (ref "BZ1") (pin "1") (pinfunction "+_1") (pintype "passive"))
      (node (ref "C27") (pin "2") (pinfunction "2_2") (pintype "passive"))
    )
    (net (code "42") (name "GND") (class "Default")
      (node (ref "C15") (pin "1") (pinfunction "1_1") (pintype "passive"))
      (node (ref "C16") (pin "1") (pinfunction "1_1") (pintype "passive"))
      (node (ref "C17") (pin "1") (pinfunction "1_1") (pintype "passive"))
      (node (ref "C18") (pin "1") (pinfunction "1_1") (pintype "passive"))
      (node (ref "C19") (pin "1") (pinfunction "1_1") (pintype "passive"))
      (node (ref "C20") (pin "1") (pinfunction "1_1") (pintype "passive"))
      (node (ref "C21") (pin "1") (pinfunction "1_1") (pintype "passive"))
      (node (ref "C22") (pin "1") (pinfunction "1_1") (pintype "passive"))
      (node (ref "C23") (pin "1") (pinfunction "1_1") (pintype "passive"))
      (node (ref "C24") (pin "1") (pinfunction "1_1") (pintype "passive"))
      (node (ref "C25") (pin "1") (pinfunction "1_1") (pintype "passive"))
      (node (ref "C26") (pin "1") (pinfunction "1_1") (pintype "passive"))
      (node (ref "C27") (pin "1") (pinfunction "1_1") (pintype "passive"))
      (node (ref "C28") (pin "1") (pinfunction "1_1") (pintype "passive"))
      (node (ref "C29") (pin "1") (pinfunction "1_1") (pintype "passive"))
      (node (ref "C30") (pin "2") (pinfunction "2_2") (pintype "passive"))
      (node (ref "C31") (pin "1") (pinfunction "1_1") (pintype "passive"))
      (node (ref "C32") (pin "1") (pinfunction "1_1") (pintype "passive"))
      (node (ref "Q3") (pin "2") (pinfunction "E_2") (pintype "passive"))
      (node (ref "Q4") (pin "2") (pinfunction "E_2") (pintype "passive"))
      (node (ref "R13") (pin "1") (pinfunction "1_1") (pintype "passive"))
      (node (ref "R7") (pin "1") (pinfunction "1_1") (pintype "passive"))
      (node (ref "U3") (pin "2") (pinfunction "GND_2") (pintype "passive"))
      (node (ref "U4") (pin "23") (pinfunction "VSS_1_23") (pintype "passive"))
      (node (ref "U4") (pin "35") (pinfunction "VSS_2_35") (pintype "passive"))
      (node (ref "U4") (pin "47") (pinfunction "VSS_3_47") (pintype "passive"))
      (node (ref "U4") (pin "8") (pinfunction "VSSA_8") (pintype "passive"))
      (node (ref "U5") (pin "1") (pinfunction "GND_1") (pintype "passive"))
      (node (ref "U5") (pin "15") (pinfunction "GND_15") (pintype "passive"))
      (node (ref "U5") (pin "38") (pinfunction "GND_38") (pintype "passive"))
      (node (ref "U5") (pin "39") (pinfunction "EPAD_39") (pintype "passive"))
      (node (ref "U6") (pin "4") (pinfunction "GND_4") (pintype "passive"))
      (node (ref "U7") (pin "4") (pinfunction "VSS_4") (pintype "passive"))
      (node (ref "X1") (pin "2") (pinfunction "GND_2") (pintype "passive"))
    )
    (net (code "43") (name "Net-(R14-Pad1)") (class "Default")
      (node (ref "R14") (pin "1") (pinfunction "1_1") (pintype "passive"))
      (node (ref "SW1") (pin "1") (pinfunction "1_1") (pintype "passive"))
    )
    (net (code "44") (name "Net-(U4-PB0)") (class "Default")
      (node (ref "R6") (pin "2") (pinfunction "2_2") (pintype "passive"))
      (node (ref "U4") (pin "18") (pinfunction "PB0_18") (pintype "passive"))
    )
    (net (code "45") (name "Net-(U4-PB14)") (class "Default")
      (node (ref "R12") (pin "2") (pinfunction "2_2") (pintype "passive"))
      (node (ref "U4") (pin "27") (pinfunction "PB14_27") (pintype "passive"))
    )
    (net (code "46") (name "unconnected-(SW1-Pad3)") (class "Default")
      (node (ref "SW1") (pin "3") (pinfunction "3_3") (pintype "passive"))
    )
    (net (code "47") (name "unconnected-(U4-PA0-WKUP-Pad10)") (class "Default")
      (node (ref "U4") (pin "10") (pinfunction "PA0-WKUP_10") (pintype "passive"))
    )
    (net (code "48") (name "unconnected-(U4-PA1-Pad11)") (class "Default")
      (node (ref "U4") (pin "11") (pinfunction "PA1_11") (pintype "passive"))
    )
    (net (code "49") (name "unconnected-(U4-PA6_{slash}_SPI1_MISO-Pad16)") (class "Default")
      (node (ref "U4") (pin "16") (pinfunction "PA6_/_SPI1_MISO_16") (pintype "passive"))
    )
    (net (code "50") (name "unconnected-(U4-PA8_{slash}_USART1_CK-Pad29)") (class "Default")
      (node (ref "U4") (pin "29") (pinfunction "PA8_/_USART1_CK_29") (pintype "passive"))
    )
    (net (code "51") (name "unconnected-(U4-PA9_{slash}_USART1_TX-Pad30)") (class "Default")
      (node (ref "U4") (pin "30") (pinfunction "PA9_/_USART1_TX_30") (pintype "passive"))
    )
    (net (code "52") (name "unconnected-(U4-PA10_{slash}_USART1_RX-Pad31)") (class "Default")
      (node (ref "U4") (pin "31") (pinfunction "PA10_/_USART1_RX_31") (pintype "passive"))
    )
    (net (code "53") (name "unconnected-(U4-PB3-Pad39)") (class "Default")
      (node (ref "U4") (pin "39") (pinfunction "PB3_39") (pintype "passive"))
    )
    (net (code "54") (name "unconnected-(U4-PB8-Pad45)") (class "Default")
      (node (ref "U4") (pin "45") (pinfunction "PB8_45") (pintype "passive"))
    )
    (net (code "55") (name "unconnected-(U4-PB12-Pad25)") (class "Default")
      (node (ref "U4") (pin "25") (pinfunction "PB12_25") (pintype "passive"))
    )
    (net (code "56") (name "unconnected-(U4-PB13-Pad26)") (class "Default")
      (node (ref "U4") (pin "26") (pinfunction "PB13_26") (pintype "passive"))
    )
    (net (code "57") (name "unconnected-(U4-PB15-Pad28)") (class "Default")
      (node (ref "U4") (pin "28") (pinfunction "PB15_28") (pintype "passive"))
    )
    (net (code "58") (name "unconnected-(U4-PC13-TAMPERRTC-Pad2)") (class "Default")
      (node (ref "U4") (pin "2") (pinfunction "PC13-TAMPERRTC_2") (pintype "passive"))
    )
    (net (code "59") (name "unconnected-(U4-PC14-OSC32_IN-Pad3)") (class "Default")
      (node (ref "U4") (pin "3") (pinfunction "PC14-OSC32_IN_3") (pintype "passive"))
    )
    (net (code "60") (name "unconnected-(U4-PC15-OSC32_OUT-Pad4)") (class "Default")
      (node (ref "U4") (pin "4") (pinfunction "PC15-OSC32_OUT_4") (pintype "passive"))
    )
    (net (code "61") (name "unconnected-(U4-VDDA-Pad9)") (class "Default")
      (node (ref "U4") (pin "9") (pinfunction "VDDA_9") (pintype "passive"))
    )
    (net (code "62") (name "unconnected-(U5-IO0-Pad25)") (class "Default")
      (node (ref "U5") (pin "25") (pinfunction "IO0_25") (pintype "passive"))
    )
    (net (code "63") (name "unconnected-(U5-IO2-Pad24)") (class "Default")
      (node (ref "U5") (pin "24") (pinfunction "IO2_24") (pintype "passive"))
    )
    (net (code "64") (name "unconnected-(U5-IO4-Pad26)") (class "Default")
      (node (ref "U5") (pin "26") (pinfunction "IO4_26") (pintype "passive"))
    )
    (net (code "65") (name "unconnected-(U5-IO5-Pad29)") (class "Default")
      (node (ref "U5") (pin "29") (pinfunction "IO5_29") (pintype "passive"))
    )
    (net (code "66") (name "unconnected-(U5-IO12-Pad14)") (class "Default")
      (node (ref "U5") (pin "14") (pinfunction "IO12_14") (pintype "passive"))
    )
    (net (code "67") (name "unconnected-(U5-IO13-Pad16)") (class "Default")
      (node (ref "U5") (pin "16") (pinfunction "IO13_16") (pintype "passive"))
    )
    (net (code "68") (name "unconnected-(U5-IO14-Pad13)") (class "Default")
      (node (ref "U5") (pin "13") (pinfunction "IO14_13") (pintype "passive"))
    )
    (net (code "69") (name "unconnected-(U5-IO15-Pad23)") (class "Default")
      (node (ref "U5") (pin "23") (pinfunction "IO15_23") (pintype "passive"))
    )
    (net (code "70") (name "unconnected-(U5-IO16-Pad27)") (class "Default")
      (node (ref "U5") (pin "27") (pinfunction "IO16_27") (pintype "passive"))
    )
    (net (code "71") (name "unconnected-(U5-IO17-Pad28)") (class "Default")
      (node (ref "U5") (pin "28") (pinfunction "IO17_28") (pintype "passive"))
    )
    (net (code "72") (name "unconnected-(U5-IO18-Pad30)") (class "Default")
      (node (ref "U5") (pin "30") (pinfunction "IO18_30") (pintype "passive"))
    )
    (net (code "73") (name "unconnected-(U5-IO19-Pad31)") (class "Default")
      (node (ref "U5") (pin "31") (pinfunction "IO19_31") (pintype "passive"))
    )
    (net (code "74") (name "unconnected-(U5-IO21-Pad33)") (class "Default")
      (node (ref "U5") (pin "33") (pinfunction "IO21_33") (pintype "passive"))
    )
    (net (code "75") (name "unconnected-(U5-IO22-Pad36)") (class "Default")
      (node (ref "U5") (pin "36") (pinfunction "IO22_36") (pintype "passive"))
    )
    (net (code "76") (name "unconnected-(U5-IO23-Pad37)") (class "Default")
      (node (ref "U5") (pin "37") (pinfunction "IO23_37") (pintype "passive"))
    )
    (net (code "77") (name "unconnected-(U5-IO25-Pad10)") (class "Default")
      (node (ref "U5") (pin "10") (pinfunction "IO25_10") (pintype "passive"))
    )
    (net (code "78") (name "unconnected-(U5-IO26-Pad11)") (class "Default")
      (node (ref "U5") (pin "11") (pinfunction "IO26_11") (pintype "passive"))
    )
    (net (code "79") (name "unconnected-(U5-IO27-Pad12)") (class "Default")
      (node (ref "U5") (pin "12") (pinfunction "IO27_12") (pintype "passive"))
    )
    (net (code "80") (name "unconnected-(U5-IO32-Pad8)") (class "Default")
      (node (ref "U5") (pin "8") (pinfunction "IO32_8") (pintype "passive"))
    )
    (net (code "81") (name "unconnected-(U5-IO33-Pad9)") (class "Default")
      (node (ref "U5") (pin "9") (pinfunction "IO33_9") (pintype "passive"))
    )
    (net (code "82") (name "unconnected-(U5-IO34-Pad6)") (class "Default")
      (node (ref "U5") (pin "6") (pinfunction "IO34_6") (pintype "passive"))
    )
    (net (code "83") (name "unconnected-(U5-IO35-Pad7)") (class "Default")
      (node (ref "U5") (pin "7") (pinfunction "IO35_7") (pintype "passive"))
    )
    (net (code "84") (name "unconnected-(U5-NC-Pad17)") (class "Default")
      (node (ref "U5") (pin "17") (pinfunction "NC_17") (pintype "passive"))
    )
    (net (code "85") (name "unconnected-(U5-NC-Pad18)") (class "Default")
      (node (ref "U5") (pin "18") (pinfunction "NC_18") (pintype "passive"))
    )
    (net (code "86") (name "unconnected-(U5-NC-Pad19)") (class "Default")
      (node (ref "U5") (pin "19") (pinfunction "NC_19") (pintype "passive"))
    )
    (net (code "87") (name "unconnected-(U5-NC-Pad20)") (class "Default")
      (node (ref "U5") (pin "20") (pinfunction "NC_20") (pintype "passive"))
    )
    (net (code "88") (name "unconnected-(U5-NC-Pad21)") (class "Default")
      (node (ref "U5") (pin "21") (pinfunction "NC_21") (pintype "passive"))
    )
    (net (code "89") (name "unconnected-(U5-NC-Pad22)") (class "Default")
      (node (ref "U5") (pin "22") (pinfunction "NC_22") (pintype "passive"))
    )
    (net (code "90") (name "unconnected-(U5-NC-Pad32)") (class "Default")
      (node (ref "U5") (pin "32") (pinfunction "NC_32") (pintype "passive"))
    )
    (net (code "91") (name "unconnected-(U5-SENSOR_VN-Pad5)") (class "Default")
      (node (ref "U5") (pin "5") (pinfunction "SENSOR_VN_5") (pintype "passive"))
    )
    (net (code "92") (name "unconnected-(U5-SENSOR_VP-Pad4)") (class "Default")
      (node (ref "U5") (pin "4") (pinfunction "SENSOR_VP_4") (pintype "passive"))
    )
    (net (code "93") (name "unconnected-(U6-NC-Pad7)") (class "Default")
      (node (ref "U6") (pin "7") (pinfunction "NC_7") (pintype "passive"))
    )
    (net (code "94") (name "unconnected-(U6-~{ALERT}-Pad6)") (class "Default")
      (node (ref "U6") (pin "6") (pinfunction "~{ALERT}_6") (pintype "passive"))
    )
    (net (code "95") (name "unconnected-(U7-FT{slash}OUT-Pad7)") (class "Default")
      (node (ref "U7") (pin "7") (pinfunction "FT/OUT_7") (pintype "passive"))
    )
  )
)
